# 2V5_DIST.net
KiCad netlist of a schematic drawn in Altium Designer
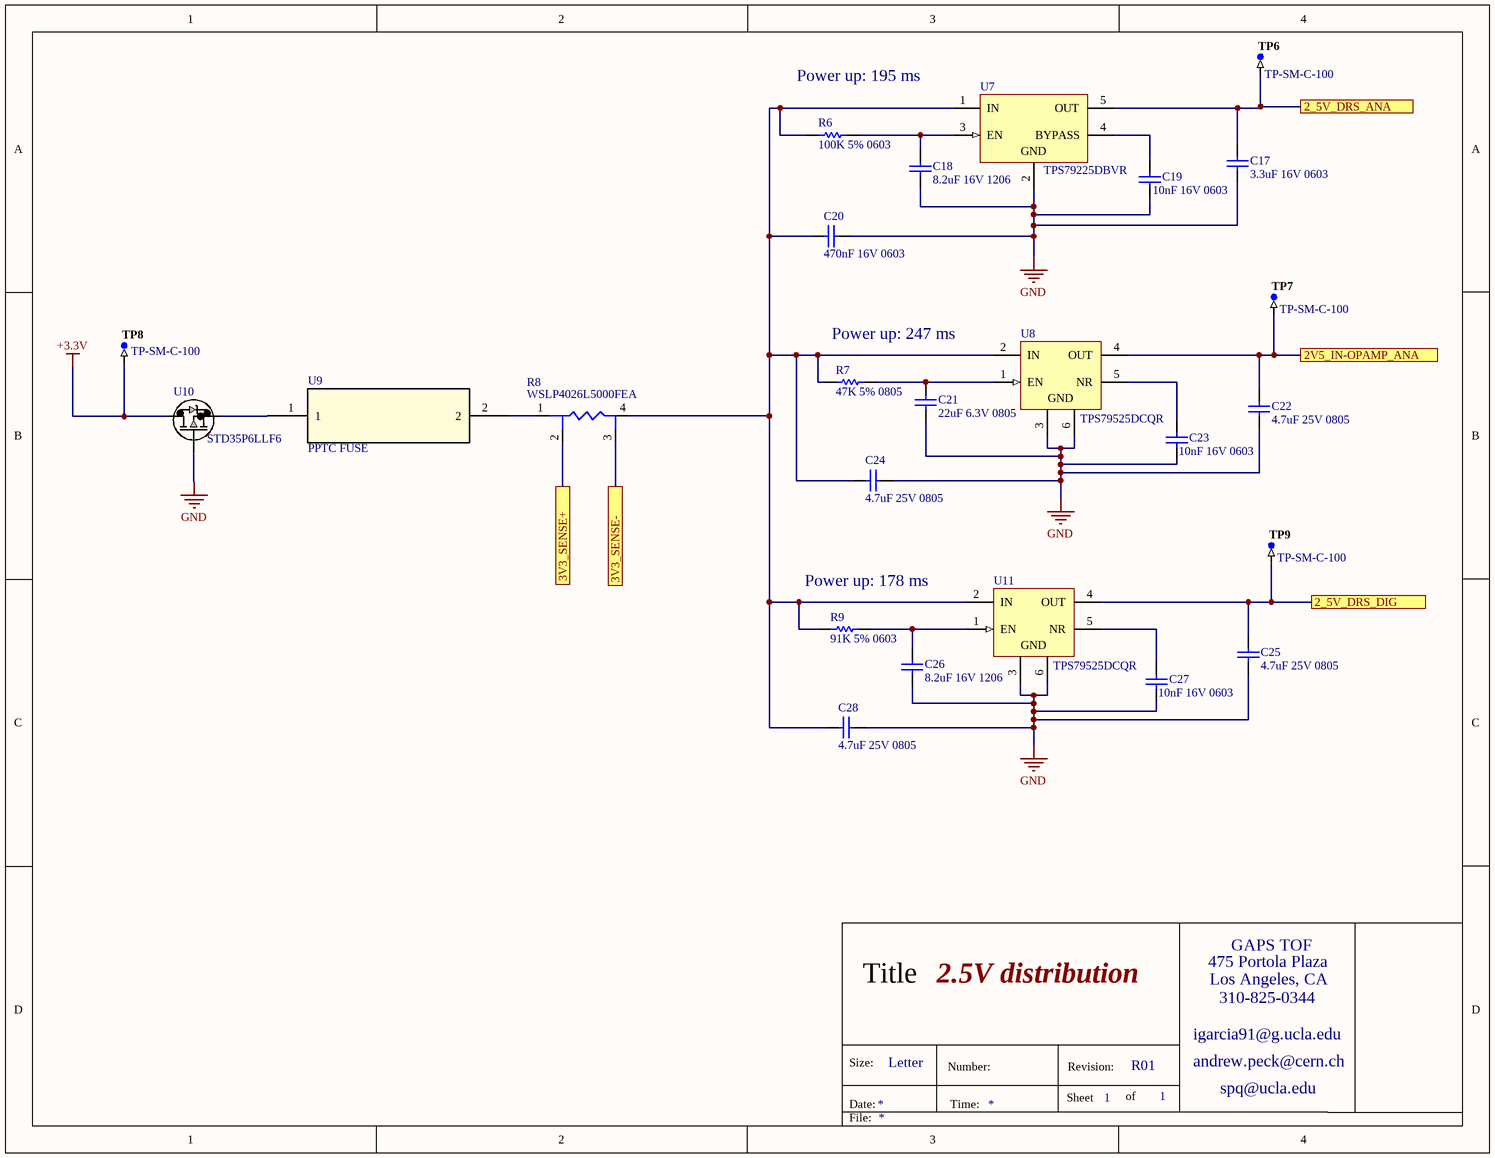
[diagram p0: 2V5_DIST.SchDoc]

(export (version "E")
  (design (tool "Eeschema 10.0.6"))
  (components
    (comp (ref "C17")
      (value "3.3uF 16V 0603")
      (footprint "CAPC0603(1608)100_L")
      (description "CAP 3.3uF 16V ±20% 0603 (1608 Metric) Thickness 1mm SMD")
      (fields (field (name "TOLERANCE") "Â±20%"))
      (libsource (lib "Altium Content Vault") (part "CAP"))
    )
    (comp (ref "C18")
      (value "8.2uF 16V 1206")
      (footprint "CAPC1206(3216)190_N")
      (description "CAP 8.2uF 16V ±20% 1206 (3216 Metric) Thickness 1.9mm SMD")
      (fields (field (name "TOLERANCE") "Â±20%"))
      (libsource (lib "Altium Content Vault") (part "CAP"))
    )
    (comp (ref "C19")
      (value "10nF 16V 0603")
      (footprint "CAPC0603(1608)100_L")
      (description "CAP 10nF 16V ±10% 0603 (1608 Metric) Thickness 1mm SMD")
      (fields (field (name "TOLERANCE") "Â±10%"))
      (libsource (lib "Altium Content Vault") (part "CAP"))
    )
    (comp (ref "C20")
      (value "470nF 16V 0603")
      (footprint "CAPC0603(1608)100_M")
      (description "CAP 470nF 16V ±10% 0603 (1608 Metric) Thickness 1mm SMD")
      (fields (field (name "TOLERANCE") "Â±10%"))
      (libsource (lib "Altium Content Vault") (part "CAP"))
    )
    (comp (ref "C21")
      (value "22uF 6.3V 0805")
      (footprint "CAPC0805(2012)145_M")
      (description "CAP 22uF 6.3V ±20% 0805 (2012 Metric) Thickness 1.45mm SMD")
      (fields (field (name "TOLERANCE") "Â±20%"))
      (libsource (lib "Altium Content Vault") (part "CAP"))
    )
    (comp (ref "C22")
      (value "4.7uF 25V 0805")
      (footprint "CAPC0805(2012)145_L")
      (description "CAP 4.7uF 25V ±10% 0805 (2012 Metric) Thickness 1.45mm SMD")
      (fields (field (name "TOLERANCE") "Â±10%"))
      (libsource (lib "Altium Content Vault") (part "CAP"))
    )
    (comp (ref "C23")
      (value "10nF 16V 0603")
      (footprint "CAPC0603(1608)100_L")
      (description "CAP 10nF 16V ±10% 0603 (1608 Metric) Thickness 1mm SMD")
      (fields (field (name "TOLERANCE") "Â±10%"))
      (libsource (lib "Altium Content Vault") (part "CAP"))
    )
    (comp (ref "C24")
      (value "4.7uF 25V 0805")
      (footprint "CAPC0805(2012)145_L")
      (description "CAP 4.7uF 25V ±10% 0805 (2012 Metric) Thickness 1.45mm SMD")
      (fields (field (name "TOLERANCE") "Â±10%"))
      (libsource (lib "Altium Content Vault") (part "CAP"))
    )
    (comp (ref "C25")
      (value "4.7uF 25V 0805")
      (footprint "CAPC0805(2012)145_L")
      (description "CAP 4.7uF 25V ±10% 0805 (2012 Metric) Thickness 1.45mm SMD")
      (fields (field (name "TOLERANCE") "Â±10%"))
      (libsource (lib "Altium Content Vault") (part "CAP"))
    )
    (comp (ref "C26")
      (value "8.2uF 16V 1206")
      (footprint "CAPC1206(3216)190_N")
      (description "CAP 8.2uF 16V ±20% 1206 (3216 Metric) Thickness 1.9mm SMD")
      (fields (field (name "TOLERANCE") "Â±20%"))
      (libsource (lib "Altium Content Vault") (part "CAP"))
    )
    (comp (ref "C27")
      (value "10nF 16V 0603")
      (footprint "CAPC0603(1608)100_L")
      (description "CAP 10nF 16V ±10% 0603 (1608 Metric) Thickness 1mm SMD")
      (fields (field (name "TOLERANCE") "Â±10%"))
      (libsource (lib "Altium Content Vault") (part "CAP"))
    )
    (comp (ref "C28")
      (value "4.7uF 25V 0805")
      (footprint "CAPC0805(2012)145_L")
      (description "CAP 4.7uF 25V ±10% 0805 (2012 Metric) Thickness 1.45mm SMD")
      (fields (field (name "TOLERANCE") "Â±10%"))
      (libsource (lib "Altium Content Vault") (part "CAP"))
    )
    (comp (ref "R6")
      (value "100K 5% 0603")
      (footprint "RESC0603(1608)_N")
      (description "100K 0.1W 5% 0603 (1608 Metric)  SMD")
      (fields (field (name "TOLERANCE") "5 %") (field (name "POWER") "0.1 W"))
      (libsource (lib "Altium Content Vault") (part "RES"))
    )
    (comp (ref "R7")
      (value "47K 5% 0805")
      (footprint "RESC0805(2012)_L")
      (description "47K 0.125W 5% 0805 (2012 Metric)  SMD")
      (fields (field (name "TOLERANCE") "5 %") (field (name "POWER") "0.125 W"))
      (libsource (lib "Altium Content Vault") (part "RES"))
    )
    (comp (ref "R8")
      (value "WSLP4026L5000FEA")
      (description "Current Sense Resistors - SMD 7watt .0005ohm 1%")
      (libsource (lib "WSLP4026L5000FEA") (part "WSLP4026L5000FEA"))
    )
    (comp (ref "R9")
      (value "91K 5% 0603")
      (footprint "RESC0603(1608)_L")
      (description "91K 0.1W 5% 0603 (1608 Metric)  SMD")
      (fields (field (name "TOLERANCE") "5 %") (field (name "POWER") "0.1 W"))
      (libsource (lib "Altium Content Vault") (part "RES"))
    )
    (comp (ref "TP6")
      (value "TP-SM-C-100")
      (footprint "TP-SM-C-100")
      (description "Test Point, Surface Mount, Circular, Pad Diameter 1 mm")
      (fields (field (name "MANUFACTURER") "No Vendor"))
      (libsource (lib "Altium Content Vault") (part "TP-SM"))
    )
    (comp (ref "TP7")
      (value "TP-SM-C-100")
      (footprint "TP-SM-C-100")
      (description "Test Point, Surface Mount, Circular, Pad Diameter 1 mm")
      (fields (field (name "MANUFACTURER") "No Vendor"))
      (libsource (lib "Altium Content Vault") (part "TP-SM"))
    )
    (comp (ref "TP8")
      (value "TP-SM-C-100")
      (footprint "TP-SM-C-100")
      (description "Test Point, Surface Mount, Circular, Pad Diameter 1 mm")
      (fields (field (name "MANUFACTURER") "No Vendor"))
      (libsource (lib "Altium Content Vault") (part "TP-SM"))
    )
    (comp (ref "TP9")
      (value "TP-SM-C-100")
      (footprint "TP-SM-C-100")
      (description "Test Point, Surface Mount, Circular, Pad Diameter 1 mm")
      (fields (field (name "MANUFACTURER") "No Vendor"))
      (libsource (lib "Altium Content Vault") (part "TP-SM"))
    )
    (comp (ref "U7")
      (value "TPS79225DBVR")
      (footprint "DBV0005A_M")
      (fields (field (name "MANUFACTURER") "Texas Instruments"))
      (libsource (lib "TPS79225DBVR") (part "CMP-0394-00239-2"))
    )
    (comp (ref "U8")
      (value "TPS79525DCQR")
      (footprint "DCQ0006A_L")
      (fields (field (name "MANUFACTURER") "Texas Instruments"))
      (libsource (lib "TPS79525DCQR") (part "CMP-0395-00444-2"))
    )
    (comp (ref "U9")
      (value "PPTC FUSE")
      (footprint "0ZCF")
      (description "Resettable Fuses - PPTC")
      (fields (field (name "MANUFACTURER_PART_NUMBER") "0ZCF0250FF2C"))
      (libsource (lib "0ZCF0250FF2C") (part "0ZCF0250FF2C"))
    )
    (comp (ref "U10")
      (value "STD35P6LLF6")
      (footprint "DPAK")
      (description "MOSFET P-channel 60 V, 0.025 Ohm typ., 35 A STripFET F6 Power MOSFET in a DPAK package")
      (fields (field (name "MANUFACTURER_PART_NUMBER") "STD35NF06T4"))
      (libsource (lib "STD35P6LLF6") (part "STD35P6LLF6"))
    )
    (comp (ref "U11")
      (value "TPS79525DCQR")
      (footprint "DCQ0006A_L")
      (fields (field (name "MANUFACTURER") "Texas Instruments"))
      (libsource (lib "TPS79525DCQR") (part "CMP-0395-00444-2"))
    )
  )
  (nets
    (net (code "1") (name "+3.3V") (class "Default")
      (node (ref "TP8") (pin "1") (pinfunction "1_1") (pintype "input"))
      (node (ref "U10") (pin "2") (pinfunction "D_2") (pintype "passive"))
    )
    (net (code "2") (name "/2V5_IN-OPAMP_ANA") (class "Default")
      (node (ref "C22") (pin "2") (pinfunction "2_2") (pintype "passive"))
      (node (ref "TP7") (pin "1") (pinfunction "1_1") (pintype "input"))
      (node (ref "U8") (pin "4") (pinfunction "OUT_4") (pintype "power_in"))
    )
    (net (code "3") (name "/2_5V_DRS_ANA") (class "Default")
      (node (ref "C17") (pin "2") (pinfunction "2_2") (pintype "passive"))
      (node (ref "TP6") (pin "1") (pinfunction "1_1") (pintype "input"))
      (node (ref "U7") (pin "5") (pinfunction "OUT_5") (pintype "power_in"))
    )
    (net (code "4") (name "/2_5V_DRS_DIG") (class "Default")
      (node (ref "C25") (pin "2") (pinfunction "2_2") (pintype "passive"))
      (node (ref "TP9") (pin "1") (pinfunction "1_1") (pintype "input"))
      (node (ref "U11") (pin "4") (pinfunction "OUT_4") (pintype "power_in"))
    )
    (net (code "5") (name "/3V3_SENSE+") (class "Default") (node (ref "R8") (pin "2") (pintype "passive")))
    (net (code "6") (name "/3V3_SENSE-") (class "Default") (node (ref "R8") (pin "3") (pintype "passive")))
    (net (code "7") (name "GND") (class "Default")
      (node (ref "C17") (pin "1") (pinfunction "1_1") (pintype "passive"))
      (node (ref "C18") (pin "1") (pinfunction "1_1") (pintype "passive"))
      (node (ref "C19") (pin "1") (pinfunction "1_1") (pintype "passive"))
      (node (ref "C20") (pin "1") (pinfunction "1_1") (pintype "passive"))
      (node (ref "C21") (pin "1") (pinfunction "1_1") (pintype "passive"))
      (node (ref "C22") (pin "1") (pinfunction "1_1") (pintype "passive"))
      (node (ref "C23") (pin "1") (pinfunction "1_1") (pintype "passive"))
      (node (ref "C24") (pin "2") (pinfunction "2_2") (pintype "passive"))
      (node (ref "C25") (pin "1") (pinfunction "1_1") (pintype "passive"))
      (node (ref "C26") (pin "1") (pinfunction "1_1") (pintype "passive"))
      (node (ref "C27") (pin "1") (pinfunction "1_1") (pintype "passive"))
      (node (ref "C28") (pin "2") (pinfunction "2_2") (pintype "passive"))
      (node (ref "U10") (pin "1") (pinfunction "G_1") (pintype "passive"))
      (node (ref "U11") (pin "3") (pinfunction "GND_3") (pintype "power_in"))
      (node (ref "U11") (pin "6") (pinfunction "GND_6") (pintype "power_in"))
      (node (ref "U7") (pin "2") (pinfunction "GND_2") (pintype "power_in"))
      (node (ref "U8") (pin "3") (pinfunction "GND_3") (pintype "power_in"))
      (node (ref "U8") (pin "6") (pinfunction "GND_6") (pintype "power_in"))
    )
    (net (code "8") (name "Net-(R8-Pad1)") (class "Default")
      (node (ref "R8") (pin "1") (pintype "passive"))
      (node (ref "U9") (pin "2") (pinfunction "2_2") (pintype "passive"))
    )
    (net (code "9") (name "Net-(U7-BYPASS)") (class "Default")
      (node (ref "C19") (pin "2") (pinfunction "2_2") (pintype "passive"))
      (node (ref "U7") (pin "4") (pinfunction "BYPASS_4") (pintype "passive"))
    )
    (net (code "10") (name "Net-(U7-EN)") (class "Default")
      (node (ref "C18") (pin "2") (pinfunction "2_2") (pintype "passive"))
      (node (ref "R6") (pin "2") (pinfunction "2_2") (pintype "passive"))
      (node (ref "U7") (pin "3") (pinfunction "EN_3") (pintype "input"))
    )
    (net (code "11") (name "Net-(U8-EN)") (class "Default")
      (node (ref "C21") (pin "2") (pinfunction "2_2") (pintype "passive"))
      (node (ref "R7") (pin "2") (pinfunction "2_2") (pintype "passive"))
      (node (ref "U8") (pin "1") (pinfunction "EN_1") (pintype "input"))
    )
    (net (code "12") (name "Net-(U8-NR)") (class "Default")
      (node (ref "C23") (pin "2") (pinfunction "2_2") (pintype "passive"))
      (node (ref "U8") (pin "5") (pinfunction "NR_5") (pintype "passive"))
    )
    (net (code "13") (name "Net-(U10-S)") (class "Default")
      (node (ref "U10") (pin "3") (pinfunction "S_3") (pintype "passive"))
      (node (ref "U9") (pin "1") (pinfunction "1_1") (pintype "passive"))
    )
    (net (code "14") (name "Net-(U11-EN)") (class "Default")
      (node (ref "C26") (pin "2") (pinfunction "2_2") (pintype "passive"))
      (node (ref "R9") (pin "2") (pinfunction "2_2") (pintype "passive"))
      (node (ref "U11") (pin "1") (pinfunction "EN_1") (pintype "input"))
    )
    (net (code "15") (name "Net-(U11-IN)") (class "Default")
      (node (ref "C20") (pin "2") (pinfunction "2_2") (pintype "passive"))
      (node (ref "C24") (pin "1") (pinfunction "1_1") (pintype "passive"))
      (node (ref "C28") (pin "1") (pinfunction "1_1") (pintype "passive"))
      (node (ref "R6") (pin "1") (pinfunction "1_1") (pintype "passive"))
      (node (ref "R7") (pin "1") (pinfunction "1_1") (pintype "passive"))
      (node (ref "R8") (pin "4") (pintype "passive"))
      (node (ref "R9") (pin "1") (pinfunction "1_1") (pintype "passive"))
      (node (ref "U11") (pin "2") (pinfunction "IN_2") (pintype "power_in"))
      (node (ref "U7") (pin "1") (pinfunction "IN_1") (pintype "power_in"))
      (node (ref "U8") (pin "2") (pinfunction "IN_2") (pintype "power_in"))
    )
    (net (code "16") (name "Net-(U11-NR)") (class "Default")
      (node (ref "C27") (pin "2") (pinfunction "2_2") (pintype "passive"))
      (node (ref "U11") (pin "5") (pinfunction "NR_5") (pintype "passive"))
    )
  )
)
